# voltage_board.net
KiCad netlist of a schematic drawn in EAGLE
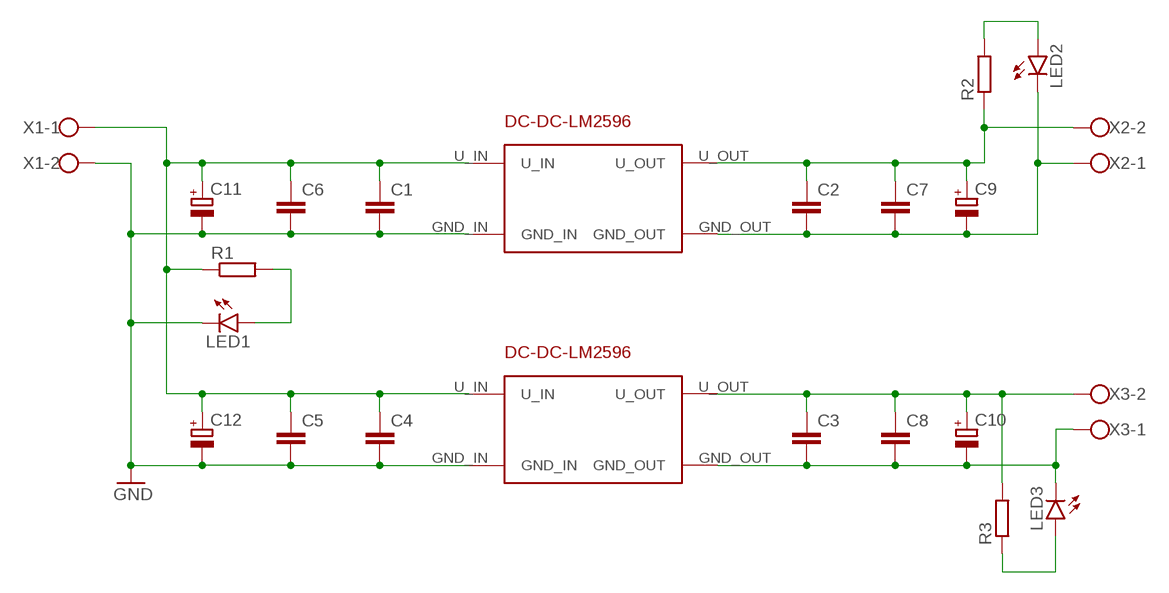
[diagram p0: schematic, sheet 1]

(export (version "E")
  (design (tool "Eeschema 10.0.6"))
  (components
    (comp (ref "C1")
      (value "C-EUC1206")
      (footprint "eagle-import:C1206")
      (libsource (lib "eagle-import") (part "C-EUC1206"))
    )
    (comp (ref "C2")
      (value "C-EUC1206")
      (footprint "eagle-import:C1206")
      (libsource (lib "eagle-import") (part "C-EUC1206"))
    )
    (comp (ref "C3")
      (value "C-EUC1206")
      (footprint "eagle-import:C1206")
      (libsource (lib "eagle-import") (part "C-EUC1206"))
    )
    (comp (ref "C4")
      (value "C-EUC1206")
      (footprint "eagle-import:C1206")
      (libsource (lib "eagle-import") (part "C-EUC1206"))
    )
    (comp (ref "C5")
      (value "C-EUC1206")
      (footprint "eagle-import:C1206")
      (libsource (lib "eagle-import") (part "C-EUC1206"))
    )
    (comp (ref "C6")
      (value "C-EUC1206")
      (footprint "eagle-import:C1206")
      (libsource (lib "eagle-import") (part "C-EUC1206"))
    )
    (comp (ref "C7")
      (value "C-EUC1206")
      (footprint "eagle-import:C1206")
      (libsource (lib "eagle-import") (part "C-EUC1206"))
    )
    (comp (ref "C8")
      (value "C-EUC1206")
      (footprint "eagle-import:C1206")
      (libsource (lib "eagle-import") (part "C-EUC1206"))
    )
    (comp (ref "C9")
      (value "CPOL-EU140CLH-0810")
      (footprint "eagle-import:140CLH-0810")
      (libsource (lib "eagle-import") (part "CPOL-EU140CLH-0810"))
    )
    (comp (ref "C10")
      (value "CPOL-EU140CLH-0810")
      (footprint "eagle-import:140CLH-0810")
      (libsource (lib "eagle-import") (part "CPOL-EU140CLH-0810"))
    )
    (comp (ref "C11")
      (value "CPOL-EU140CLH-0810")
      (footprint "eagle-import:140CLH-0810")
      (libsource (lib "eagle-import") (part "CPOL-EU140CLH-0810"))
    )
    (comp (ref "C12")
      (value "CPOL-EU140CLH-0810")
      (footprint "eagle-import:140CLH-0810")
      (libsource (lib "eagle-import") (part "CPOL-EU140CLH-0810"))
    )
    (comp (ref "LED1")
      (value "LEDSML1206")
      (footprint "eagle-import:SML1206")
      (libsource (lib "eagle-import") (part "LEDSML1206"))
    )
    (comp (ref "LED2")
      (value "LEDSML1206")
      (footprint "eagle-import:SML1206")
      (libsource (lib "eagle-import") (part "LEDSML1206"))
    )
    (comp (ref "LED3")
      (value "LEDSML1206")
      (footprint "eagle-import:SML1206")
      (libsource (lib "eagle-import") (part "LEDSML1206"))
    )
    (comp (ref "R1")
      (value "R-EU_M1206")
      (footprint "eagle-import:M1206")
      (libsource (lib "eagle-import") (part "R-EU_M1206"))
    )
    (comp (ref "R2")
      (value "R-EU_M1206")
      (footprint "eagle-import:M1206")
      (libsource (lib "eagle-import") (part "R-EU_M1206"))
    )
    (comp (ref "R3")
      (value "R-EU_M1206")
      (footprint "eagle-import:M1206")
      (libsource (lib "eagle-import") (part "R-EU_M1206"))
    )
    (comp (ref "U$1")
      (value "DC-DC-LM2596")
      (footprint "eagle-import:DC-DC-LM2596")
      (libsource (lib "eagle-import") (part "DC-DC-LM2596"))
    )
    (comp (ref "U$2")
      (value "DC-DC-LM2596")
      (footprint "eagle-import:DC-DC-LM2596")
      (libsource (lib "eagle-import") (part "DC-DC-LM2596"))
    )
    (comp (ref "X1")
      (value "W237-102")
      (footprint "eagle-import:W237-102")
      (fields (field (name "MPN") "237-102"))
      (libsource (lib "eagle-import") (part "W237-102"))
    )
    (comp (ref "X2")
      (value "W237-102")
      (footprint "eagle-import:W237-102")
      (fields (field (name "MPN") "237-102"))
      (libsource (lib "eagle-import") (part "W237-102"))
    )
    (comp (ref "X3")
      (value "W237-102")
      (footprint "eagle-import:W237-102")
      (fields (field (name "MPN") "237-102"))
      (libsource (lib "eagle-import") (part "W237-102"))
    )
  )
  (nets
    (net (code "1") (name "GND") (class "Default")
      (node (ref "C1") (pin "2") (pinfunction "2_2") (pintype "passive"))
      (node (ref "C11") (pin "-") (pinfunction "-_-") (pintype "passive"))
      (node (ref "C12") (pin "-") (pinfunction "-_-") (pintype "passive"))
      (node (ref "C4") (pin "2") (pinfunction "2_2") (pintype "passive"))
      (node (ref "C5") (pin "2") (pinfunction "2_2") (pintype "passive"))
      (node (ref "C6") (pin "2") (pinfunction "2_2") (pintype "passive"))
      (node (ref "LED1") (pin "C") (pinfunction "C_C") (pintype "passive"))
      (node (ref "U$1") (pin "GND_IN") (pinfunction "GND_IN_GND_IN") (pintype "bidirectional"))
      (node (ref "U$2") (pin "GND_IN") (pinfunction "GND_IN_GND_IN") (pintype "bidirectional"))
      (node (ref "X1") (pin "2") (pinfunction "KL_2") (pintype "passive"))
    )
    (net (code "2") (name "Net-(LED1-PadA)") (class "Default")
      (node (ref "LED1") (pin "A") (pinfunction "A_A") (pintype "passive"))
      (node (ref "R1") (pin "2") (pinfunction "2_2") (pintype "passive"))
    )
    (net (code "3") (name "Net-(LED2-PadA)") (class "Default")
      (node (ref "LED2") (pin "A") (pinfunction "A_A") (pintype "passive"))
      (node (ref "R2") (pin "2") (pinfunction "2_2") (pintype "passive"))
    )
    (net (code "4") (name "Net-(LED3-PadA)") (class "Default")
      (node (ref "LED3") (pin "A") (pinfunction "A_A") (pintype "passive"))
      (node (ref "R3") (pin "1") (pinfunction "1_1") (pintype "passive"))
    )
    (net (code "5") (name "Net-(X1A-KL)") (class "Default")
      (node (ref "C1") (pin "1") (pinfunction "1_1") (pintype "passive"))
      (node (ref "C11") (pin "+") (pinfunction "+_+") (pintype "passive"))
      (node (ref "C12") (pin "+") (pinfunction "+_+") (pintype "passive"))
      (node (ref "C4") (pin "1") (pinfunction "1_1") (pintype "passive"))
      (node (ref "C5") (pin "1") (pinfunction "1_1") (pintype "passive"))
      (node (ref "C6") (pin "1") (pinfunction "1_1") (pintype "passive"))
      (node (ref "R1") (pin "1") (pinfunction "1_1") (pintype "passive"))
      (node (ref "U$1") (pin "U_IN") (pinfunction "U_IN_U_IN") (pintype "bidirectional"))
      (node (ref "U$2") (pin "U_IN") (pinfunction "U_IN_U_IN") (pintype "bidirectional"))
      (node (ref "X1") (pin "1") (pinfunction "KL_1") (pintype "passive"))
    )
    (net (code "6") (name "Net-(X2A-KL)") (class "Default")
      (node (ref "C2") (pin "2") (pinfunction "2_2") (pintype "passive"))
      (node (ref "C7") (pin "2") (pinfunction "2_2") (pintype "passive"))
      (node (ref "C9") (pin "-") (pinfunction "-_-") (pintype "passive"))
      (node (ref "LED2") (pin "C") (pinfunction "C_C") (pintype "passive"))
      (node (ref "U$1") (pin "GND_OUT") (pinfunction "GND_OUT_GND_OUT") (pintype "bidirectional"))
      (node (ref "X2") (pin "1") (pinfunction "KL_1") (pintype "passive"))
    )
    (net (code "7") (name "Net-(X2B-KL)") (class "Default")
      (node (ref "C2") (pin "1") (pinfunction "1_1") (pintype "passive"))
      (node (ref "C7") (pin "1") (pinfunction "1_1") (pintype "passive"))
      (node (ref "C9") (pin "+") (pinfunction "+_+") (pintype "passive"))
      (node (ref "R2") (pin "1") (pinfunction "1_1") (pintype "passive"))
      (node (ref "U$1") (pin "U_OUT") (pinfunction "U_OUT_U_OUT") (pintype "bidirectional"))
      (node (ref "X2") (pin "2") (pinfunction "KL_2") (pintype "passive"))
    )
    (net (code "8") (name "Net-(X3A-KL)") (class "Default")
      (node (ref "C10") (pin "-") (pinfunction "-_-") (pintype "passive"))
      (node (ref "C3") (pin "2") (pinfunction "2_2") (pintype "passive"))
      (node (ref "C8") (pin "2") (pinfunction "2_2") (pintype "passive"))
      (node (ref "LED3") (pin "C") (pinfunction "C_C") (pintype "passive"))
      (node (ref "U$2") (pin "GND_OUT") (pinfunction "GND_OUT_GND_OUT") (pintype "bidirectional"))
      (node (ref "X3") (pin "1") (pinfunction "KL_1") (pintype "passive"))
    )
    (net (code "9") (name "Net-(X3B-KL)") (class "Default")
      (node (ref "C10") (pin "+") (pinfunction "+_+") (pintype "passive"))
      (node (ref "C3") (pin "1") (pinfunction "1_1") (pintype "passive"))
      (node (ref "C8") (pin "1") (pinfunction "1_1") (pintype "passive"))
      (node (ref "R3") (pin "2") (pinfunction "2_2") (pintype "passive"))
      (node (ref "U$2") (pin "U_OUT") (pinfunction "U_OUT_U_OUT") (pintype "bidirectional"))
      (node (ref "X3") (pin "2") (pinfunction "KL_2") (pintype "passive"))
    )
  )
)
